# SMT_2inch_printer_060903.net
KiCad netlist of a schematic drawn in Altium Designer
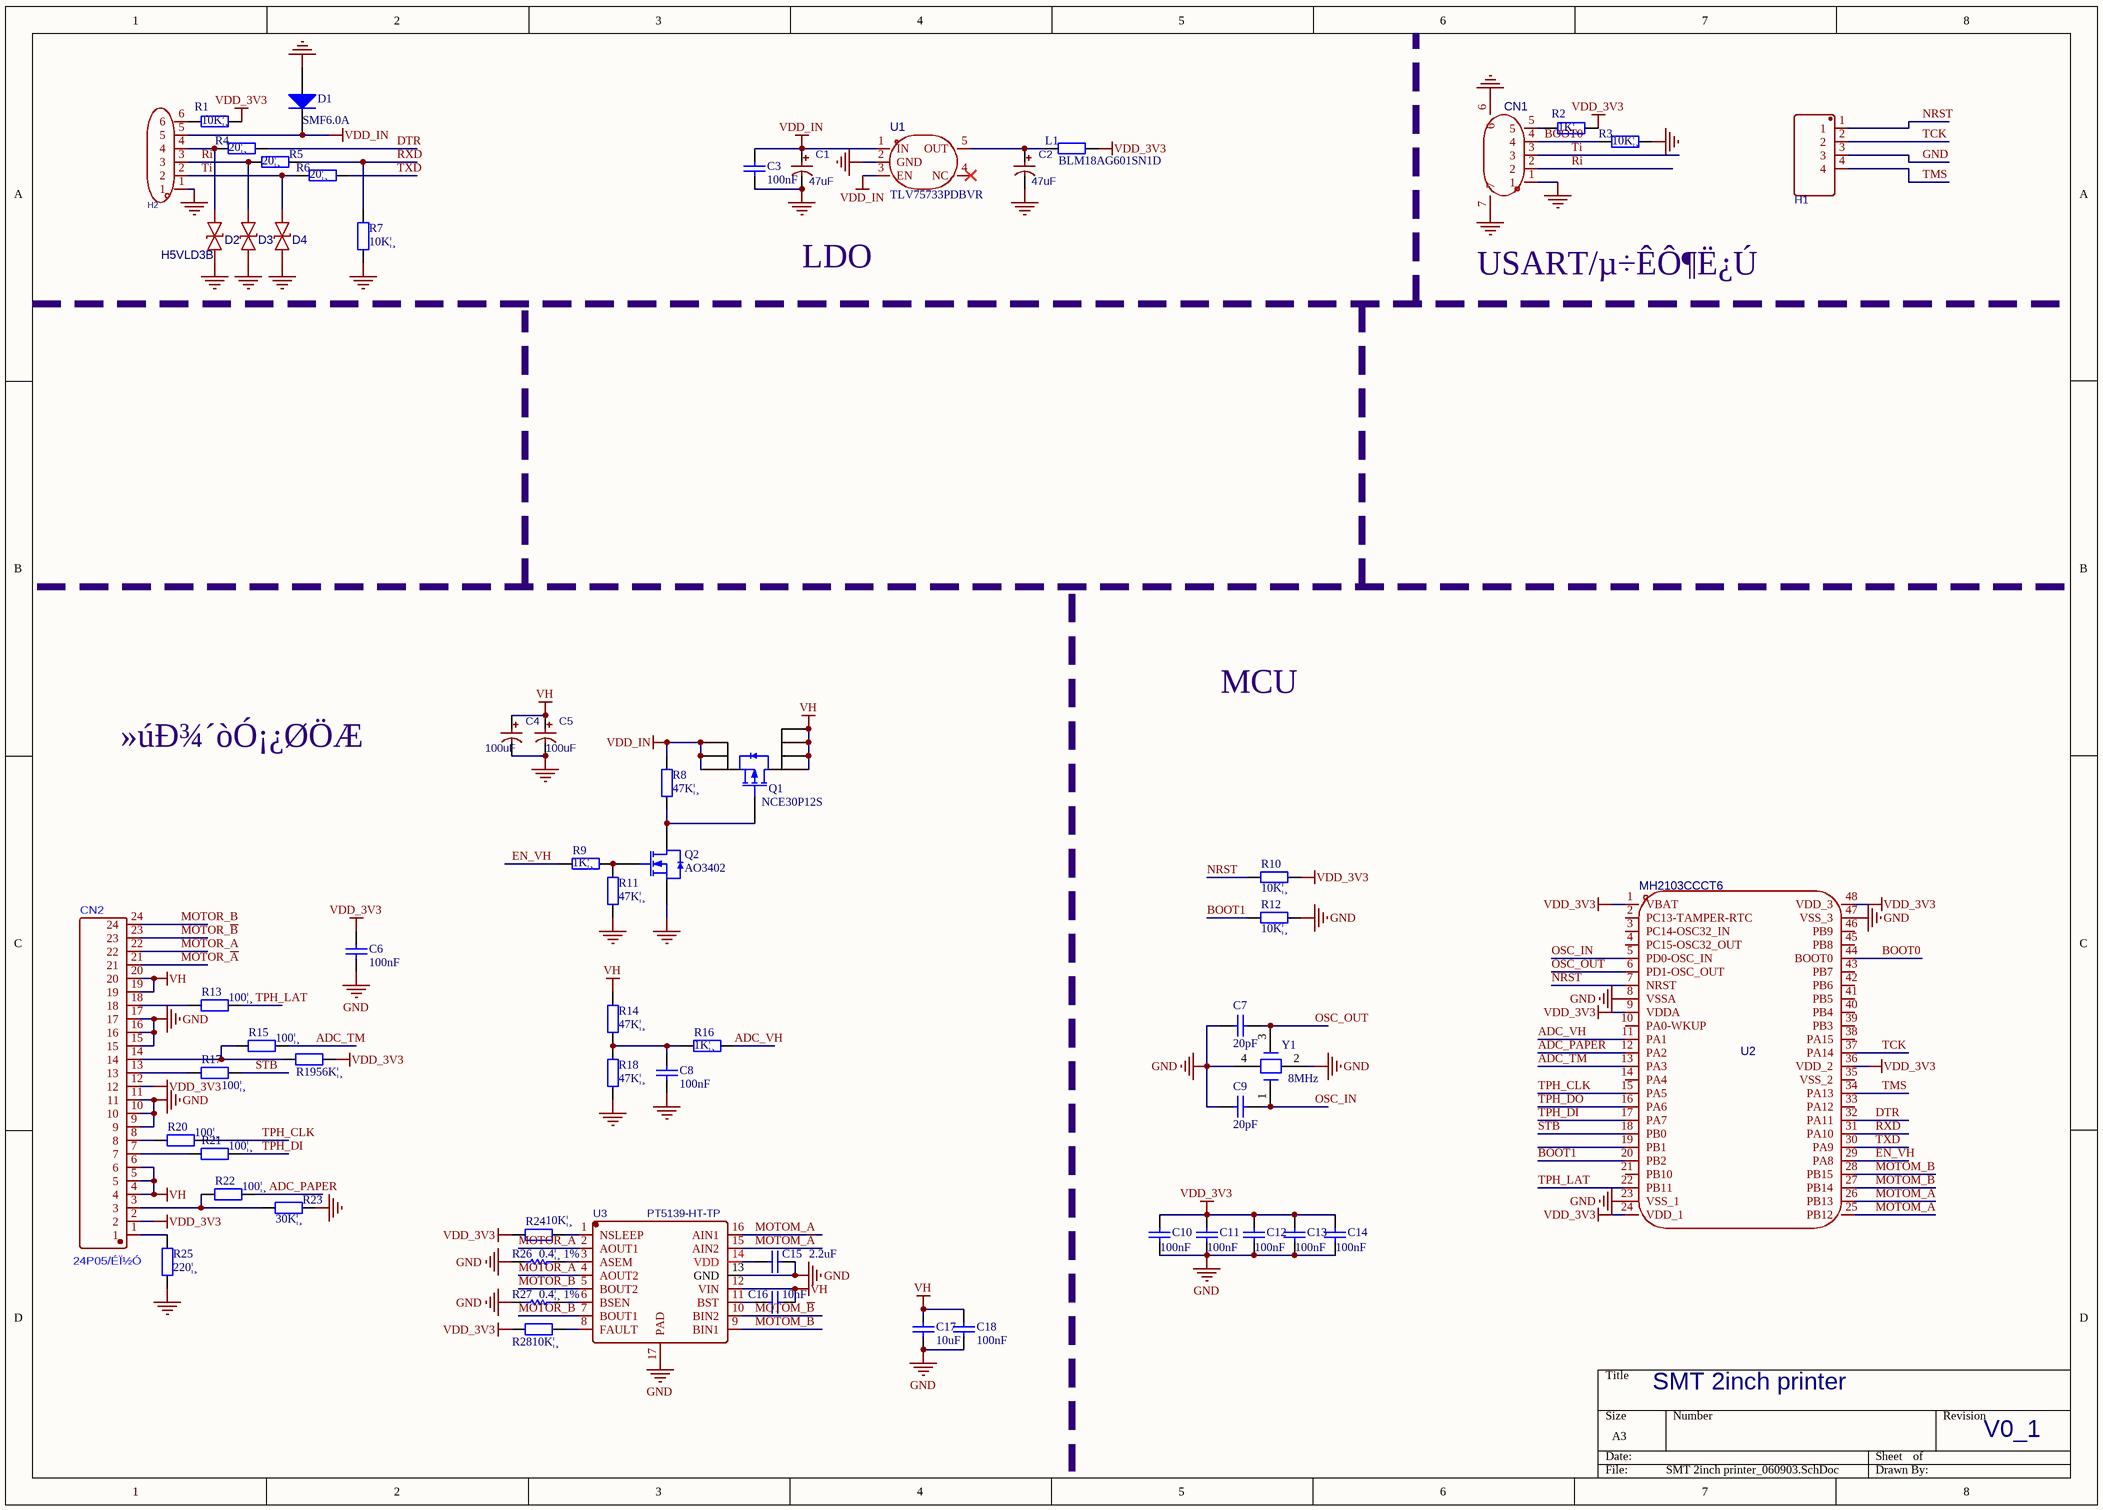
[diagram p0: SMT 2inch printer_060903.SchDoc]

(export (version "E")
  (design (tool "Eeschema 10.0.6"))
  (components
    (comp (ref "C1")
      (value "47uF")
      (footprint "CAP-SMD_BD6.3-L6.6-W6.6-FD")
      (fields
        (field (name "BOM_MANUFACTURER PART") "10uF 25V RHOS")
        (field (name "BOM_SUPPLIER PART") "C19576")
      )
      (libsource (lib "*") (part "10uF"))
    )
    (comp (ref "C2")
      (value "47uF")
      (footprint "CAP-SMD_BD6.3-L6.6-W6.6-FD")
      (fields
        (field (name "BOM_MANUFACTURER PART") "10uF 25V RHOS")
        (field (name "BOM_SUPPLIER PART") "C19576")
      )
      (libsource (lib "*") (part "10uF"))
    )
    (comp (ref "C3")
      (value "100nF")
      (footprint "0603_C")
      (description "贴片电容")
      (libsource (lib "*") (part "0603 100nF (104) 10% 50V"))
    )
    (comp (ref "C4")
      (value "100uF")
      (footprint "CAP-SMD_BD6.3-L6.6-W6.6-FD")
      (fields
        (field (name "BOM_MANUFACTURER PART") "10uF 25V RHOS")
        (field (name "BOM_SUPPLIER PART") "C19576")
      )
      (libsource (lib "*") (part "10uF"))
    )
    (comp (ref "C5")
      (value "100uF")
      (footprint "CAP-SMD_BD6.3-L6.6-W6.6-FD")
      (fields
        (field (name "BOM_MANUFACTURER PART") "10uF 25V RHOS")
        (field (name "BOM_SUPPLIER PART") "C19576")
      )
      (libsource (lib "*") (part "10uF"))
    )
    (comp (ref "C6")
      (value "100nF")
      (footprint "0603_C")
      (description "贴片电容")
      (libsource (lib "Miscellaneous Devices LC") (part "0603 100nF (104) 10% 50V"))
    )
    (comp (ref "C7")
      (value "20pF")
      (footprint "0603_C")
      (description "贴片电容")
      (libsource (lib "Miscellaneous Devices LC") (part "0603 10pF (100) 5% 50V"))
    )
    (comp (ref "C8")
      (value "100nF")
      (footprint "0603_C")
      (description "贴片电容")
      (libsource (lib "Miscellaneous Devices LC") (part "0603 100nF (104) 10% 50V"))
    )
    (comp (ref "C9")
      (value "20pF")
      (footprint "0603_C")
      (description "贴片电容")
      (libsource (lib "Miscellaneous Devices LC") (part "0603 10pF (100) 5% 50V"))
    )
    (comp (ref "C10")
      (value "100nF")
      (footprint "0603_C")
      (description "贴片电容")
      (libsource (lib "Miscellaneous Devices LC") (part "0603 100nF (104) 10% 50V"))
    )
    (comp (ref "C11")
      (value "100nF")
      (footprint "0603_C")
      (description "贴片电容")
      (libsource (lib "Miscellaneous Devices LC") (part "0603 100nF (104) 10% 50V"))
    )
    (comp (ref "C12")
      (value "100nF")
      (footprint "0603_C")
      (description "贴片电容")
      (libsource (lib "Miscellaneous Devices LC") (part "0603 100nF (104) 10% 50V"))
    )
    (comp (ref "C13")
      (value "100nF")
      (footprint "0603_C")
      (description "贴片电容")
      (libsource (lib "Miscellaneous Devices LC") (part "0603 100nF (104) 10% 50V"))
    )
    (comp (ref "C14")
      (value "100nF")
      (footprint "0603_C")
      (description "贴片电容")
      (libsource (lib "Miscellaneous Devices LC") (part "0603 100nF (104) 10% 50V"))
    )
    (comp (ref "C15")
      (value "2.2uF")
      (footprint "0603_C")
      (description "贴片电容")
      (libsource (lib "Miscellaneous Devices LC") (part "0805 2.2uF (225) 20% 50V"))
    )
    (comp (ref "C16")
      (value "10nF")
      (footprint "0603_C")
      (description "贴片电容")
      (libsource (lib "Miscellaneous Devices LC") (part "0603 10nF (103) 10% 50V"))
    )
    (comp (ref "C17")
      (value "10uF")
      (footprint "0603_C")
      (description "贴片电容")
      (libsource (lib "Miscellaneous Devices LC") (part "0805 10uF (106) 10% 25V"))
    )
    (comp (ref "C18")
      (value "100nF")
      (footprint "0603_C")
      (description "贴片电容")
      (libsource (lib "Miscellaneous Devices LC") (part "0603 100nF (104) 10% 50V"))
    )
    (comp (ref "CN1")
      (value "mx1.25mm-5p-wt")
      (footprint "CONN-SMD_5P-P1.25_MX1.25MM-5P-WT")
      (fields (field (name "MANUFACTURERPART") "MX1.25mm-5P-WT"))
      (libsource (lib "altium-import") (part "root_2_mx1.25mm-5p-wt_"))
    )
    (comp (ref "CN2")
      (value "24P05/上接")
      (footprint "FPC-SMD_24P-P0.50_F0500WR-S-24PNLNG1GB0R")
      (libsource (lib "altium-import") (part "root_2__"))
    )
    (comp (ref "D1")
      (value "SMF6.0A")
      (footprint "SOD-123FL_L2.7-W1.8-LS3.8-RD")
      (description "稳压二极管")
      (libsource (lib "*") (part "SOD-323 1N4148WS T4"))
    )
    (comp (ref "D2")
      (value "H5VLD3B")
      (footprint "SOD-323_L1.7-W1.3-LS2.5-BI")
      (libsource (lib "altium-import") (part "root_1_PESD5V0S1BA_C2827694_"))
    )
    (comp (ref "D3")
      (value "H5VLD3B")
      (footprint "SOD-323_L1.7-W1.3-LS2.5-BI")
      (libsource (lib "altium-import") (part "root_1_PESD5V0S1BA_C2827694_"))
    )
    (comp (ref "D4")
      (value "H5VLD3B")
      (footprint "SOD-323_L1.7-W1.3-LS2.5-BI")
      (libsource (lib "altium-import") (part "root_1_PESD5V0S1BA_C2827694_"))
    )
    (comp (ref "H1")
      (value "77311-462K05LF")
      (footprint "77311-462K05LF")
      (fields (field (name "BOM_SUPPLIER PART") "C180219") (field (name "CONTRIBUTOR") "LCSC"))
      (libsource (lib "*") (part "77311-462K05LF"))
    )
    (comp (ref "H2")
      (value "lail-pz2.54-6p-l")
      (footprint "HDR-TH_6P-P2.54-V-F")
      (fields (field (name "MANUFACTURERPART") "LAIL-PZ2.54-6P-L"))
      (libsource (lib "altium-import") (part "root_2_lail-pz2.54-6p-l_"))
    )
    (comp (ref "L1")
      (value "BLM18AG601SN1D")
      (footprint "0805_L")
      (description "贴片电阻")
      (libsource (lib "") (part "0603 4.7KΩ (4701) 1%_1"))
    )
    (comp (ref "Q1")
      (value "NCE30P12S")
      (footprint "SOIC-8_150mil")
      (description "MOS(场效应管)")
      (libsource (lib "*") (part "AO4407A"))
    )
    (comp (ref "Q2")
      (value "AO3402")
      (footprint "SOT-23-3L")
      (description "MOS(场效应管)")
      (libsource (lib "*") (part "AO3402A N道沟 X0YV1T SOT-23"))
    )
    (comp (ref "R1")
      (value "10KΩ")
      (footprint "0603_R")
      (description "贴片电阻")
      (libsource (lib "") (part "0603 4.7KΩ (4701) 1%_1"))
    )
    (comp (ref "R2")
      (value "1KΩ")
      (footprint "0603_R")
      (description "贴片电阻")
      (libsource (lib "") (part "0603 4.7KΩ (4701) 1%_1"))
    )
    (comp (ref "R3")
      (value "10KΩ")
      (footprint "0603_R")
      (description "贴片电阻")
      (libsource (lib "") (part "0603 4.7KΩ (4701) 1%_1"))
    )
    (comp (ref "R4")
      (value "20Ω")
      (footprint "0603_R")
      (description "贴片电阻")
      (libsource (lib "*") (part "0603 100Ω (1000) 1%"))
    )
    (comp (ref "R5")
      (value "20Ω")
      (footprint "0603_R")
      (description "贴片电阻")
      (libsource (lib "*") (part "0603 100Ω (1000) 1%"))
    )
    (comp (ref "R6")
      (value "20Ω")
      (footprint "0603_R")
      (description "贴片电阻")
      (libsource (lib "*") (part "0603 100Ω (1000) 1%"))
    )
    (comp (ref "R7")
      (value "10KΩ")
      (footprint "0603_R")
      (description "贴片电阻")
      (libsource (lib "") (part "0603 4.7KΩ (4701) 1%_2"))
    )
    (comp (ref "R8")
      (value "47KΩ")
      (footprint "0603_R")
      (description "贴片电阻")
      (libsource (lib "*") (part "0603 47KΩ (4702) 1%"))
    )
    (comp (ref "R9")
      (value "1KΩ")
      (footprint "0603_R")
      (description "贴片电阻")
      (libsource (lib "*") (part "0603 470Ω (4700) 1%"))
    )
    (comp (ref "R10")
      (value "10KΩ")
      (footprint "0603_R")
      (description "贴片电阻")
      (libsource (lib "Miscellaneous Devices LC") (part "0603 4.7KΩ (4701) 1%"))
    )
    (comp (ref "R11")
      (value "47KΩ")
      (footprint "0603_R")
      (description "贴片电阻")
      (libsource (lib "*") (part "0603 4.7KΩ (4701) 1%"))
    )
    (comp (ref "R12")
      (value "10KΩ")
      (footprint "0603_R")
      (description "贴片电阻")
      (libsource (lib "Miscellaneous Devices LC") (part "0603 4.7KΩ (4701) 1%"))
    )
    (comp (ref "R13")
      (value "100Ω")
      (footprint "0603_R")
      (description "贴片电阻")
      (libsource (lib "Miscellaneous Devices LC") (part "0603 10KΩ (1002) 1%"))
    )
    (comp (ref "R14")
      (value "47KΩ")
      (footprint "0603_R")
      (description "贴片电阻")
      (libsource (lib "*") (part "0603 4.7KΩ (4701) 1%"))
    )
    (comp (ref "R15")
      (value "100Ω")
      (footprint "0603_R")
      (description "贴片电阻")
      (libsource (lib "Miscellaneous Devices LC") (part "0603 10KΩ (1002) 1%"))
    )
    (comp (ref "R16")
      (value "1KΩ")
      (footprint "0603_R")
      (description "贴片电阻")
      (libsource (lib "*") (part "0603 470Ω (4700) 1%"))
    )
    (comp (ref "R17")
      (value "100Ω")
      (footprint "0603_R")
      (description "贴片电阻")
      (libsource (lib "Miscellaneous Devices LC") (part "0603 10KΩ (1002) 1%"))
    )
    (comp (ref "R18")
      (value "47KΩ")
      (footprint "0603_R")
      (description "贴片电阻")
      (libsource (lib "*") (part "0603 4.7KΩ (4701) 1%"))
    )
    (comp (ref "R19")
      (value "56KΩ")
      (footprint "0603_R")
      (description "贴片电阻")
      (libsource (lib "Miscellaneous Devices LC") (part "0603 10KΩ (1002) 1%"))
    )
    (comp (ref "R20")
      (value "100Ω")
      (footprint "0603_R")
      (description "贴片电阻")
      (libsource (lib "Miscellaneous Devices LC") (part "0603 10KΩ (1002) 1%"))
    )
    (comp (ref "R21")
      (value "100Ω")
      (footprint "0603_R")
      (description "贴片电阻")
      (libsource (lib "Miscellaneous Devices LC") (part "0603 10KΩ (1002) 1%"))
    )
    (comp (ref "R22")
      (value "100Ω")
      (footprint "0603_R")
      (description "贴片电阻")
      (libsource (lib "Miscellaneous Devices LC") (part "0603 10KΩ (1002) 1%"))
    )
    (comp (ref "R23")
      (value "30KΩ")
      (footprint "0603_R")
      (description "贴片电阻")
      (libsource (lib "*") (part "0603 30KΩ (3002) 1%"))
    )
    (comp (ref "R24")
      (value "10KΩ")
      (footprint "0603_R")
      (description "贴片电阻")
      (libsource (lib "AD封装2018.9.19Miscellaneous Devices LC") (part "0603 10KΩ (1002) 1%"))
    )
    (comp (ref "R25")
      (value "220Ω")
      (footprint "0603_R")
      (description "贴片电阻")
      (libsource (lib "*") (part "0603 200Ω (2000) 1%"))
    )
    (comp (ref "R26")
      (value "0.4Ω 1%")
      (footprint "1206_R")
      (description "Resistor")
      (fields (field (name "PUBLISHER") "Altium Limited"))
      (libsource (lib "JM320") (part "Res"))
    )
    (comp (ref "R27")
      (value "0.4Ω 1%")
      (footprint "1206_R")
      (description "Resistor")
      (fields (field (name "PUBLISHER") "Altium Limited"))
      (libsource (lib "JM320") (part "Res"))
    )
    (comp (ref "R28")
      (value "10KΩ")
      (footprint "0603_R")
      (description "贴片电阻")
      (libsource (lib "AD封装2018.9.19Miscellaneous Devices LC") (part "0603 10KΩ (1002) 1%"))
    )
    (comp (ref "U1")
      (value "TLV75733PDBVR")
      (footprint "SOT-23-5")
      (libsource (lib "*") (part "TLV75733PDBVR"))
    )
    (comp (ref "U2")
      (value "MH2103CCCT6")
      (footprint "LQFP-48_L7.0-W7.0-P0.50-LS9.0-BL")
      (fields (field (name "MANUFACTURERPART") "STM32F103C8T6"))
      (libsource (lib "altium-import") (part "root_0_stm32f103c8t6_"))
    )
    (comp (ref "U3")
      (value "PT5139-HT-TP")
      (footprint "HTSSOP-16_L5.0-W4.4-P0.65-LS6.4-BL-EP")
      (fields (field (name "BOM_SUPPLIER PART") "C336601") (field (name "CONTRIBUTOR") "LCSC"))
      (libsource (lib "altium-import") (part "root_0_PT5139-HT-TP_"))
    )
    (comp (ref "Y1")
      (value "8MHz")
      (footprint "XT_3225_4")
      (description "Crystal Oscillator")
      (libsource (lib "JM320") (part "XTAL_4"))
    )
  )
  (nets
    (net (code "1") (name "/ADC_PAPER") (class "Default")
      (node (ref "R22") (pin "2") (pinfunction "2_2") (pintype "passive"))
      (node (ref "U2") (pin "12") (pinfunction "PA2_12") (pintype "passive"))
    )
    (net (code "2") (name "/ADC_TM") (class "Default")
      (node (ref "R15") (pin "2") (pinfunction "2_2") (pintype "passive"))
      (node (ref "U2") (pin "13") (pinfunction "PA3_13") (pintype "passive"))
    )
    (net (code "3") (name "/ADC_VH") (class "Default")
      (node (ref "R16") (pin "1") (pinfunction "1_1") (pintype "passive"))
      (node (ref "U2") (pin "11") (pinfunction "PA1_11") (pintype "passive"))
    )
    (net (code "4") (name "/BOOT0") (class "Default")
      (node (ref "CN1") (pin "4") (pinfunction "4_4") (pintype "passive"))
      (node (ref "R3") (pin "1") (pinfunction "1_1") (pintype "passive"))
      (node (ref "U2") (pin "44") (pinfunction "BOOT0_44") (pintype "passive"))
    )
    (net (code "5") (name "/BOOT1") (class "Default")
      (node (ref "R12") (pin "2") (pinfunction "2_2") (pintype "passive"))
      (node (ref "U2") (pin "20") (pinfunction "PB2_20") (pintype "passive"))
    )
    (net (code "6") (name "/DTR") (class "Default")
      (node (ref "R4") (pin "2") (pinfunction "2_2") (pintype "passive"))
      (node (ref "U2") (pin "32") (pinfunction "PA11_32") (pintype "passive"))
    )
    (net (code "7") (name "/EN_VH") (class "Default")
      (node (ref "R9") (pin "2") (pinfunction "2_2") (pintype "passive"))
      (node (ref "U2") (pin "29") (pinfunction "PA8_29") (pintype "passive"))
    )
    (net (code "8") (name "/MOTOM_A") (class "Default")
      (node (ref "U2") (pin "25") (pinfunction "PB12_25") (pintype "passive"))
      (node (ref "U3") (pin "16") (pinfunction "AIN1_16") (pintype "passive"))
    )
    (net (code "9") (name "/MOTOM_B") (class "Default")
      (node (ref "U2") (pin "28") (pinfunction "PB15_28") (pintype "passive"))
      (node (ref "U3") (pin "9") (pinfunction "BIN1_9") (pintype "passive"))
    )
    (net (code "10") (name "/MOTOM_~{A}") (class "Default")
      (node (ref "U2") (pin "26") (pinfunction "PB13_26") (pintype "passive"))
      (node (ref "U3") (pin "15") (pinfunction "AIN2_15") (pintype "passive"))
    )
    (net (code "11") (name "/MOTOM_~{B}") (class "Default")
      (node (ref "U2") (pin "27") (pinfunction "PB14_27") (pintype "passive"))
      (node (ref "U3") (pin "10") (pinfunction "BIN2_10") (pintype "passive"))
    )
    (net (code "12") (name "/MOTOR_A") (class "Default")
      (node (ref "CN2") (pin "22") (pinfunction "22_22") (pintype "passive"))
      (node (ref "U3") (pin "2") (pinfunction "AOUT1_2") (pintype "passive"))
    )
    (net (code "13") (name "/MOTOR_B") (class "Default")
      (node (ref "CN2") (pin "24") (pinfunction "24_24") (pintype "passive"))
      (node (ref "U3") (pin "7") (pinfunction "BOUT1_7") (pintype "passive"))
    )
    (net (code "14") (name "/MOTOR_~{A}") (class "Default")
      (node (ref "CN2") (pin "21") (pinfunction "21_21") (pintype "passive"))
      (node (ref "U3") (pin "4") (pinfunction "AOUT2_4") (pintype "passive"))
    )
    (net (code "15") (name "/MOTOR_~{B}") (class "Default")
      (node (ref "CN2") (pin "23") (pinfunction "23_23") (pintype "passive"))
      (node (ref "U3") (pin "5") (pinfunction "BOUT2_5") (pintype "passive"))
    )
    (net (code "16") (name "/NRST") (class "Default")
      (node (ref "H1") (pin "1") (pinfunction "1_1") (pintype "passive"))
      (node (ref "R10") (pin "2") (pinfunction "2_2") (pintype "passive"))
      (node (ref "U2") (pin "7") (pinfunction "NRST_7") (pintype "passive"))
    )
    (net (code "17") (name "/OSC_IN") (class "Default")
      (node (ref "C9") (pin "2") (pinfunction "2_2") (pintype "passive"))
      (node (ref "U2") (pin "5") (pinfunction "PD0-OSC_IN_5") (pintype "passive"))
      (node (ref "Y1") (pin "1") (pinfunction "OSC1_1") (pintype "passive"))
    )
    (net (code "18") (name "/OSC_OUT") (class "Default")
      (node (ref "C7") (pin "2") (pinfunction "2_2") (pintype "passive"))
      (node (ref "U2") (pin "6") (pinfunction "PD1-OSC_OUT_6") (pintype "passive"))
      (node (ref "Y1") (pin "3") (pinfunction "OSC2_3") (pintype "passive"))
    )
    (net (code "19") (name "/RXD") (class "Default")
      (node (ref "R5") (pin "2") (pinfunction "2_2") (pintype "passive"))
      (node (ref "R7") (pin "2") (pinfunction "2_2") (pintype "passive"))
      (node (ref "U2") (pin "31") (pinfunction "PA10_31") (pintype "passive"))
    )
    (net (code "20") (name "/Ri") (class "Default")
      (node (ref "CN1") (pin "2") (pinfunction "2_2") (pintype "passive"))
      (node (ref "D3") (pin "2") (pinfunction "2_2") (pintype "passive"))
      (node (ref "H2") (pin "3") (pinfunction "3_3") (pintype "passive"))
      (node (ref "R5") (pin "1") (pinfunction "1_1") (pintype "passive"))
    )
    (net (code "21") (name "/STB") (class "Default")
      (node (ref "R17") (pin "2") (pinfunction "2_2") (pintype "passive"))
      (node (ref "U2") (pin "18") (pinfunction "PB0_18") (pintype "passive"))
    )
    (net (code "22") (name "/TCK") (class "Default")
      (node (ref "H1") (pin "2") (pinfunction "2_2") (pintype "passive"))
      (node (ref "U2") (pin "37") (pinfunction "PA14_37") (pintype "passive"))
    )
    (net (code "23") (name "/TMS") (class "Default")
      (node (ref "H1") (pin "4") (pinfunction "4_4") (pintype "passive"))
      (node (ref "U2") (pin "34") (pinfunction "PA13_34") (pintype "passive"))
    )
    (net (code "24") (name "/TPH_CLK") (class "Default")
      (node (ref "R20") (pin "2") (pinfunction "2_2") (pintype "passive"))
      (node (ref "U2") (pin "15") (pinfunction "PA5_15") (pintype "passive"))
    )
    (net (code "25") (name "/TPH_DI") (class "Default")
      (node (ref "R21") (pin "2") (pinfunction "2_2") (pintype "passive"))
      (node (ref "U2") (pin "17") (pinfunction "PA7_17") (pintype "passive"))
    )
    (net (code "26") (name "/TPH_DO") (class "Default")
      (node (ref "U2") (pin "16") (pinfunction "PA6_16") (pintype "passive"))
    )
    (net (code "27") (name "/TPH_LAT") (class "Default")
      (node (ref "R13") (pin "2") (pinfunction "2_2") (pintype "passive"))
      (node (ref "U2") (pin "22") (pinfunction "PB11_22") (pintype "passive"))
    )
    (net (code "28") (name "/TXD") (class "Default")
      (node (ref "R6") (pin "2") (pinfunction "2_2") (pintype "passive"))
      (node (ref "U2") (pin "30") (pinfunction "PA9_30") (pintype "passive"))
    )
    (net (code "29") (name "/Ti") (class "Default")
      (node (ref "CN1") (pin "3") (pinfunction "3_3") (pintype "passive"))
      (node (ref "D4") (pin "2") (pinfunction "2_2") (pintype "passive"))
      (node (ref "H2") (pin "2") (pinfunction "2_2") (pintype "passive"))
      (node (ref "R6") (pin "1") (pinfunction "1_1") (pintype "passive"))
    )
    (net (code "30") (name "GND") (class "Default")
      (node (ref "C1") (pin "2") (pinfunction "2_2") (pintype "passive"))
      (node (ref "C10") (pin "1") (pinfunction "1_1") (pintype "passive"))
      (node (ref "C11") (pin "1") (pinfunction "1_1") (pintype "passive"))
      (node (ref "C12") (pin "1") (pinfunction "1_1") (pintype "passive"))
      (node (ref "C13") (pin "1") (pinfunction "1_1") (pintype "passive"))
      (node (ref "C14") (pin "1") (pinfunction "1_1") (pintype "passive"))
      (node (ref "C15") (pin "2") (pinfunction "2_2") (pintype "passive"))
      (node (ref "C17") (pin "1") (pinfunction "1_1") (pintype "passive"))
      (node (ref "C18") (pin "1") (pinfunction "1_1") (pintype "passive"))
      (node (ref "C2") (pin "2") (pinfunction "2_2") (pintype "passive"))
      (node (ref "C3") (pin "2") (pinfunction "2_2") (pintype "passive"))
      (node (ref "C4") (pin "2") (pinfunction "2_2") (pintype "passive"))
      (node (ref "C5") (pin "2") (pinfunction "2_2") (pintype "passive"))
      (node (ref "C6") (pin "1") (pinfunction "1_1") (pintype "passive"))
      (node (ref "C7") (pin "1") (pinfunction "1_1") (pintype "passive"))
      (node (ref "C8") (pin "1") (pinfunction "1_1") (pintype "passive"))
      (node (ref "C9") (pin "1") (pinfunction "1_1") (pintype "passive"))
      (node (ref "CN1") (pin "1") (pinfunction "1_1") (pintype "passive"))
      (node (ref "CN1") (pin "6") (pinfunction "6_6") (pintype "passive"))
      (node (ref "CN1") (pin "7") (pinfunction "7_7") (pintype "passive"))
      (node (ref "CN2") (pin "10") (pinfunction "10_10") (pintype "passive"))
      (node (ref "CN2") (pin "11") (pinfunction "11_11") (pintype "passive"))
      (node (ref "CN2") (pin "15") (pinfunction "15_15") (pintype "passive"))
      (node (ref "CN2") (pin "16") (pinfunction "16_16") (pintype "passive"))
      (node (ref "CN2") (pin "17") (pinfunction "17_17") (pintype "passive"))
      (node (ref "CN2") (pin "9") (pinfunction "9_9") (pintype "passive"))
      (node (ref "D1") (pin "1") (pinfunction "A_1") (pintype "passive"))
      (node (ref "D2") (pin "1") (pinfunction "1_1") (pintype "passive"))
      (node (ref "D3") (pin "1") (pinfunction "1_1") (pintype "passive"))
      (node (ref "D4") (pin "1") (pinfunction "1_1") (pintype "passive"))
      (node (ref "H1") (pin "3") (pinfunction "3_3") (pintype "passive"))
      (node (ref "H2") (pin "1") (pinfunction "1_1") (pintype "passive"))
      (node (ref "Q2") (pin "2") (pinfunction "S_2") (pintype "passive"))
      (node (ref "R11") (pin "2") (pinfunction "2_2") (pintype "passive"))
      (node (ref "R12") (pin "1") (pinfunction "1_1") (pintype "passive"))
      (node (ref "R18") (pin "2") (pinfunction "2_2") (pintype "passive"))
      (node (ref "R23") (pin "2") (pinfunction "2_2") (pintype "passive"))
      (node (ref "R25") (pin "1") (pinfunction "1_1") (pintype "passive"))
      (node (ref "R26") (pin "2") (pinfunction "2_2") (pintype "passive"))
      (node (ref "R27") (pin "2") (pinfunction "2_2") (pintype "passive"))
      (node (ref "R3") (pin "2") (pinfunction "2_2") (pintype "passive"))
      (node (ref "R7") (pin "1") (pinfunction "1_1") (pintype "passive"))
      (node (ref "U1") (pin "2") (pinfunction "GND_2") (pintype "passive"))
      (node (ref "U2") (pin "23") (pinfunction "VSS_1_23") (pintype "passive"))
      (node (ref "U2") (pin "47") (pinfunction "VSS_3_47") (pintype "passive"))
      (node (ref "U2") (pin "8") (pinfunction "VSSA_8") (pintype "passive"))
      (node (ref "U3") (pin "13") (pinfunction "GND_13") (pintype "passive"))
      (node (ref "U3") (pin "17") (pinfunction "PAD_17") (pintype "passive"))
      (node (ref "Y1") (pin "2") (pinfunction "5_2") (pintype "passive"))
      (node (ref "Y1") (pin "4") (pinfunction "4_4") (pintype "passive"))
    )
    (net (code "31") (name "Net-(C8-Pad2)") (class "Default")
      (node (ref "C8") (pin "2") (pinfunction "2_2") (pintype "passive"))
      (node (ref "R14") (pin "2") (pinfunction "2_2") (pintype "passive"))
      (node (ref "R16") (pin "2") (pinfunction "2_2") (pintype "passive"))
      (node (ref "R18") (pin "1") (pinfunction "1_1") (pintype "passive"))
    )
    (net (code "32") (name "Net-(CN1-Pad5)") (class "Default")
      (node (ref "CN1") (pin "5") (pinfunction "5_5") (pintype "passive"))
      (node (ref "R2") (pin "1") (pinfunction "1_1") (pintype "passive"))
    )
    (net (code "33") (name "Net-(CN2-Pad1)") (class "Default")
      (node (ref "CN2") (pin "1") (pinfunction "1_1") (pintype "passive"))
      (node (ref "R25") (pin "2") (pinfunction "2_2") (pintype "passive"))
    )
    (net (code "34") (name "Net-(CN2-Pad3)") (class "Default")
      (node (ref "CN2") (pin "3") (pinfunction "3_3") (pintype "passive"))
      (node (ref "R22") (pin "1") (pinfunction "1_1") (pintype "passive"))
      (node (ref "R23") (pin "1") (pinfunction "1_1") (pintype "passive"))
    )
    (net (code "35") (name "Net-(CN2-Pad7)") (class "Default")
      (node (ref "CN2") (pin "7") (pinfunction "7_7") (pintype "passive"))
      (node (ref "R21") (pin "1") (pinfunction "1_1") (pintype "passive"))
    )
    (net (code "36") (name "Net-(CN2-Pad8)") (class "Default")
      (node (ref "CN2") (pin "8") (pinfunction "8_8") (pintype "passive"))
      (node (ref "R20") (pin "1") (pinfunction "1_1") (pintype "passive"))
    )
    (net (code "37") (name "Net-(CN2-Pad13)") (class "Default")
      (node (ref "CN2") (pin "13") (pinfunction "13_13") (pintype "passive"))
      (node (ref "R17") (pin "1") (pinfunction "1_1") (pintype "passive"))
    )
    (net (code "38") (name "Net-(CN2-Pad14)") (class "Default")
      (node (ref "CN2") (pin "14") (pinfunction "14_14") (pintype "passive"))
      (node (ref "R15") (pin "1") (pinfunction "1_1") (pintype "passive"))
      (node (ref "R19") (pin "1") (pinfunction "1_1") (pintype "passive"))
    )
    (net (code "39") (name "Net-(CN2-Pad18)") (class "Default")
      (node (ref "CN2") (pin "18") (pinfunction "18_18") (pintype "passive"))
      (node (ref "R13") (pin "1") (pinfunction "1_1") (pintype "passive"))
    )
    (net (code "40") (name "Net-(D2-Pad2)") (class "Default")
      (node (ref "D2") (pin "2") (pinfunction "2_2") (pintype "passive"))
      (node (ref "H2") (pin "4") (pinfunction "4_4") (pintype "passive"))
      (node (ref "R4") (pin "1") (pinfunction "1_1") (pintype "passive"))
    )
    (net (code "41") (name "Net-(H2-Pad6)") (class "Default")
      (node (ref "H2") (pin "6") (pinfunction "6_6") (pintype "passive"))
      (node (ref "R1") (pin "1") (pinfunction "1_1") (pintype "passive"))
    )
    (net (code "42") (name "Net-(Q1-G)") (class "Default")
      (node (ref "Q1") (pin "4") (pinfunction "G_4") (pintype "passive"))
      (node (ref "Q2") (pin "3") (pinfunction "D_3") (pintype "passive"))
      (node (ref "R8") (pin "1") (pinfunction "1_1") (pintype "passive"))
    )
    (net (code "43") (name "Net-(Q2-G)") (class "Default")
      (node (ref "Q2") (pin "1") (pinfunction "G_1") (pintype "passive"))
      (node (ref "R11") (pin "1") (pinfunction "1_1") (pintype "passive"))
      (node (ref "R9") (pin "1") (pinfunction "1_1") (pintype "passive"))
    )
    (net (code "44") (name "Net-(U1-OUT)") (class "Default")
      (node (ref "C2") (pin "1") (pinfunction "1_1") (pintype "passive"))
      (node (ref "L1") (pin "1") (pinfunction "1_1") (pintype "passive"))
      (node (ref "U1") (pin "5") (pinfunction "OUT_5") (pintype "passive"))
    )
    (net (code "45") (name "Net-(U3-ASEM)") (class "Default")
      (node (ref "R26") (pin "1") (pinfunction "1_1") (pintype "passive"))
      (node (ref "U3") (pin "3") (pinfunction "ASEM_3") (pintype "passive"))
    )
    (net (code "46") (name "Net-(U3-BSEN)") (class "Default")
      (node (ref "R27") (pin "1") (pinfunction "1_1") (pintype "passive"))
      (node (ref "U3") (pin "6") (pinfunction "BSEN_6") (pintype "passive"))
    )
    (net (code "47") (name "Net-(U3-BST)") (class "Default")
      (node (ref "C16") (pin "1") (pinfunction "1_1") (pintype "passive"))
      (node (ref "U3") (pin "11") (pinfunction "BST_11") (pintype "passive"))
    )
    (net (code "48") (name "Net-(U3-FAULT)") (class "Default")
      (node (ref "R28") (pin "1") (pinfunction "1_1") (pintype "passive"))
      (node (ref "U3") (pin "8") (pinfunction "FAULT_8") (pintype "passive"))
    )
    (net (code "49") (name "Net-(U3-NSLEEP)") (class "Default")
      (node (ref "R24") (pin "1") (pinfunction "1_1") (pintype "passive"))
      (node (ref "U3") (pin "1") (pinfunction "NSLEEP_1") (pintype "passive"))
    )
    (net (code "50") (name "Net-(U3-VDD)") (class "Default")
      (node (ref "C15") (pin "1") (pinfunction "1_1") (pintype "passive"))
      (node (ref "U3") (pin "14") (pinfunction "VDD_14") (pintype "passive"))
    )
    (net (code "51") (name "VDD_3V3") (class "Default")
      (node (ref "C10") (pin "2") (pinfunction "2_2") (pintype "passive"))
      (node (ref "C11") (pin "2") (pinfunction "2_2") (pintype "passive"))
      (node (ref "C12") (pin "2") (pinfunction "2_2") (pintype "passive"))
      (node (ref "C13") (pin "2") (pinfunction "2_2") (pintype "passive"))
      (node (ref "C14") (pin "2") (pinfunction "2_2") (pintype "passive"))
      (node (ref "C6") (pin "2") (pinfunction "2_2") (pintype "passive"))
      (node (ref "CN2") (pin "12") (pinfunction "12_12") (pintype "passive"))
      (node (ref "CN2") (pin "2") (pinfunction "2_2") (pintype "passive"))
      (node (ref "L1") (pin "2") (pinfunction "2_2") (pintype "passive"))
      (node (ref "R1") (pin "2") (pinfunction "2_2") (pintype "passive"))
      (node (ref "R10") (pin "1") (pinfunction "1_1") (pintype "passive"))
      (node (ref "R19") (pin "2") (pinfunction "2_2") (pintype "passive"))
      (node (ref "R2") (pin "2") (pinfunction "2_2") (pintype "passive"))
      (node (ref "R24") (pin "2") (pinfunction "2_2") (pintype "passive"))
      (node (ref "R28") (pin "2") (pinfunction "2_2") (pintype "passive"))
      (node (ref "U2") (pin "1") (pinfunction "VBAT_1") (pintype "passive"))
      (node (ref "U2") (pin "24") (pinfunction "VDD_1_24") (pintype "passive"))
      (node (ref "U2") (pin "36") (pinfunction "VDD_2_36") (pintype "passive"))
      (node (ref "U2") (pin "48") (pinfunction "VDD_3_48") (pintype "passive"))
      (node (ref "U2") (pin "9") (pinfunction "VDDA_9") (pintype "passive"))
    )
    (net (code "52") (name "VDD_IN") (class "Default")
      (node (ref "C1") (pin "1") (pinfunction "1_1") (pintype "passive"))
      (node (ref "C3") (pin "1") (pinfunction "1_1") (pintype "passive"))
      (node (ref "D1") (pin "2") (pinfunction "K_2") (pintype "passive"))
      (node (ref "H2") (pin "5") (pinfunction "5_5") (pintype "passive"))
      (node (ref "Q1") (pin "1") (pinfunction "S_1") (pintype "passive"))
      (node (ref "Q1") (pin "2") (pinfunction "S_2") (pintype "passive"))
      (node (ref "Q1") (pin "3") (pinfunction "S_3") (pintype "passive"))
      (node (ref "R8") (pin "2") (pinfunction "2_2") (pintype "passive"))
      (node (ref "U1") (pin "1") (pinfunction "IN_1") (pintype "passive"))
      (node (ref "U1") (pin "3") (pinfunction "EN_3") (pintype "passive"))
    )
    (net (code "53") (name "VH") (class "Default")
      (node (ref "C16") (pin "2") (pinfunction "2_2") (pintype "passive"))
      (node (ref "C17") (pin "2") (pinfunction "2_2") (pintype "passive"))
      (node (ref "C18") (pin "2") (pinfunction "2_2") (pintype "passive"))
      (node (ref "C4") (pin "1") (pinfunction "1_1") (pintype "passive"))
      (node (ref "C5") (pin "1") (pinfunction "1_1") (pintype "passive"))
      (node (ref "CN2") (pin "19") (pinfunction "19_19") (pintype "passive"))
      (node (ref "CN2") (pin "20") (pinfunction "20_20") (pintype "passive"))
      (node (ref "CN2") (pin "4") (pinfunction "4_4") (pintype "passive"))
      (node (ref "CN2") (pin "5") (pinfunction "5_5") (pintype "passive"))
      (node (ref "CN2") (pin "6") (pinfunction "6_6") (pintype "passive"))
      (node (ref "Q1") (pin "5") (pinfunction "D_5") (pintype "passive"))
      (node (ref "Q1") (pin "6") (pinfunction "D_6") (pintype "passive"))
      (node (ref "Q1") (pin "7") (pinfunction "D_7") (pintype "passive"))
      (node (ref "Q1") (pin "8") (pinfunction "D_8") (pintype "passive"))
      (node (ref "R14") (pin "1") (pinfunction "1_1") (pintype "passive"))
      (node (ref "U3") (pin "12") (pinfunction "VIN_12") (pintype "passive"))
    )
    (net (code "54") (name "unconnected-(U1-NC-Pad4)") (class "Default")
      (node (ref "U1") (pin "4") (pinfunction "NC_4") (pintype "passive+no_connect"))
    )
    (net (code "55") (name "unconnected-(U2-PA0-WKUP-Pad10)") (class "Default")
      (node (ref "U2") (pin "10") (pinfunction "PA0-WKUP_10") (pintype "passive"))
    )
    (net (code "56") (name "unconnected-(U2-PA4-Pad14)") (class "Default")
      (node (ref "U2") (pin "14") (pinfunction "PA4_14") (pintype "passive"))
    )
    (net (code "57") (name "unconnected-(U2-PA12-Pad33)") (class "Default")
      (node (ref "U2") (pin "33") (pinfunction "PA12_33") (pintype "passive"))
    )
    (net (code "58") (name "unconnected-(U2-PA15-Pad38)") (class "Default")
      (node (ref "U2") (pin "38") (pinfunction "PA15_38") (pintype "passive"))
    )
    (net (code "59") (name "unconnected-(U2-PB1-Pad19)") (class "Default")
      (node (ref "U2") (pin "19") (pinfunction "PB1_19") (pintype "passive"))
    )
    (net (code "60") (name "unconnected-(U2-PB3-Pad39)") (class "Default")
      (node (ref "U2") (pin "39") (pinfunction "PB3_39") (pintype "passive"))
    )
    (net (code "61") (name "unconnected-(U2-PB4-Pad40)") (class "Default")
      (node (ref "U2") (pin "40") (pinfunction "PB4_40") (pintype "passive"))
    )
    (net (code "62") (name "unconnected-(U2-PB5-Pad41)") (class "Default")
      (node (ref "U2") (pin "41") (pinfunction "PB5_41") (pintype "passive"))
    )
    (net (code "63") (name "unconnected-(U2-PB6-Pad42)") (class "Default")
      (node (ref "U2") (pin "42") (pinfunction "PB6_42") (pintype "passive"))
    )
    (net (code "64") (name "unconnected-(U2-PB7-Pad43)") (class "Default")
      (node (ref "U2") (pin "43") (pinfunction "PB7_43") (pintype "passive"))
    )
    (net (code "65") (name "unconnected-(U2-PB8-Pad45)") (class "Default")
      (node (ref "U2") (pin "45") (pinfunction "PB8_45") (pintype "passive"))
    )
    (net (code "66") (name "unconnected-(U2-PB9-Pad46)") (class "Default")
      (node (ref "U2") (pin "46") (pinfunction "PB9_46") (pintype "passive"))
    )
    (net (code "67") (name "unconnected-(U2-PB10-Pad21)") (class "Default")
      (node (ref "U2") (pin "21") (pinfunction "PB10_21") (pintype "passive"))
    )
    (net (code "68") (name "unconnected-(U2-PC13-TAMPER-RTC-Pad2)") (class "Default")
      (node (ref "U2") (pin "2") (pinfunction "PC13-TAMPER-RTC_2") (pintype "passive"))
    )
    (net (code "69") (name "unconnected-(U2-PC14-OSC32_IN-Pad3)") (class "Default")
      (node (ref "U2") (pin "3") (pinfunction "PC14-OSC32_IN_3") (pintype "passive"))
    )
    (net (code "70") (name "unconnected-(U2-PC15-OSC32_OUT-Pad4)") (class "Default")
      (node (ref "U2") (pin "4") (pinfunction "PC15-OSC32_OUT_4") (pintype "passive"))
    )
    (net (code "71") (name "unconnected-(U2-VSS_2-Pad35)") (class "Default")
      (node (ref "U2") (pin "35") (pinfunction "VSS_2_35") (pintype "passive"))
    )
  )
)
